# LSU_4_9_OpenAFR_MainBoard.net
KiCad netlist of a schematic drawn in EAGLE
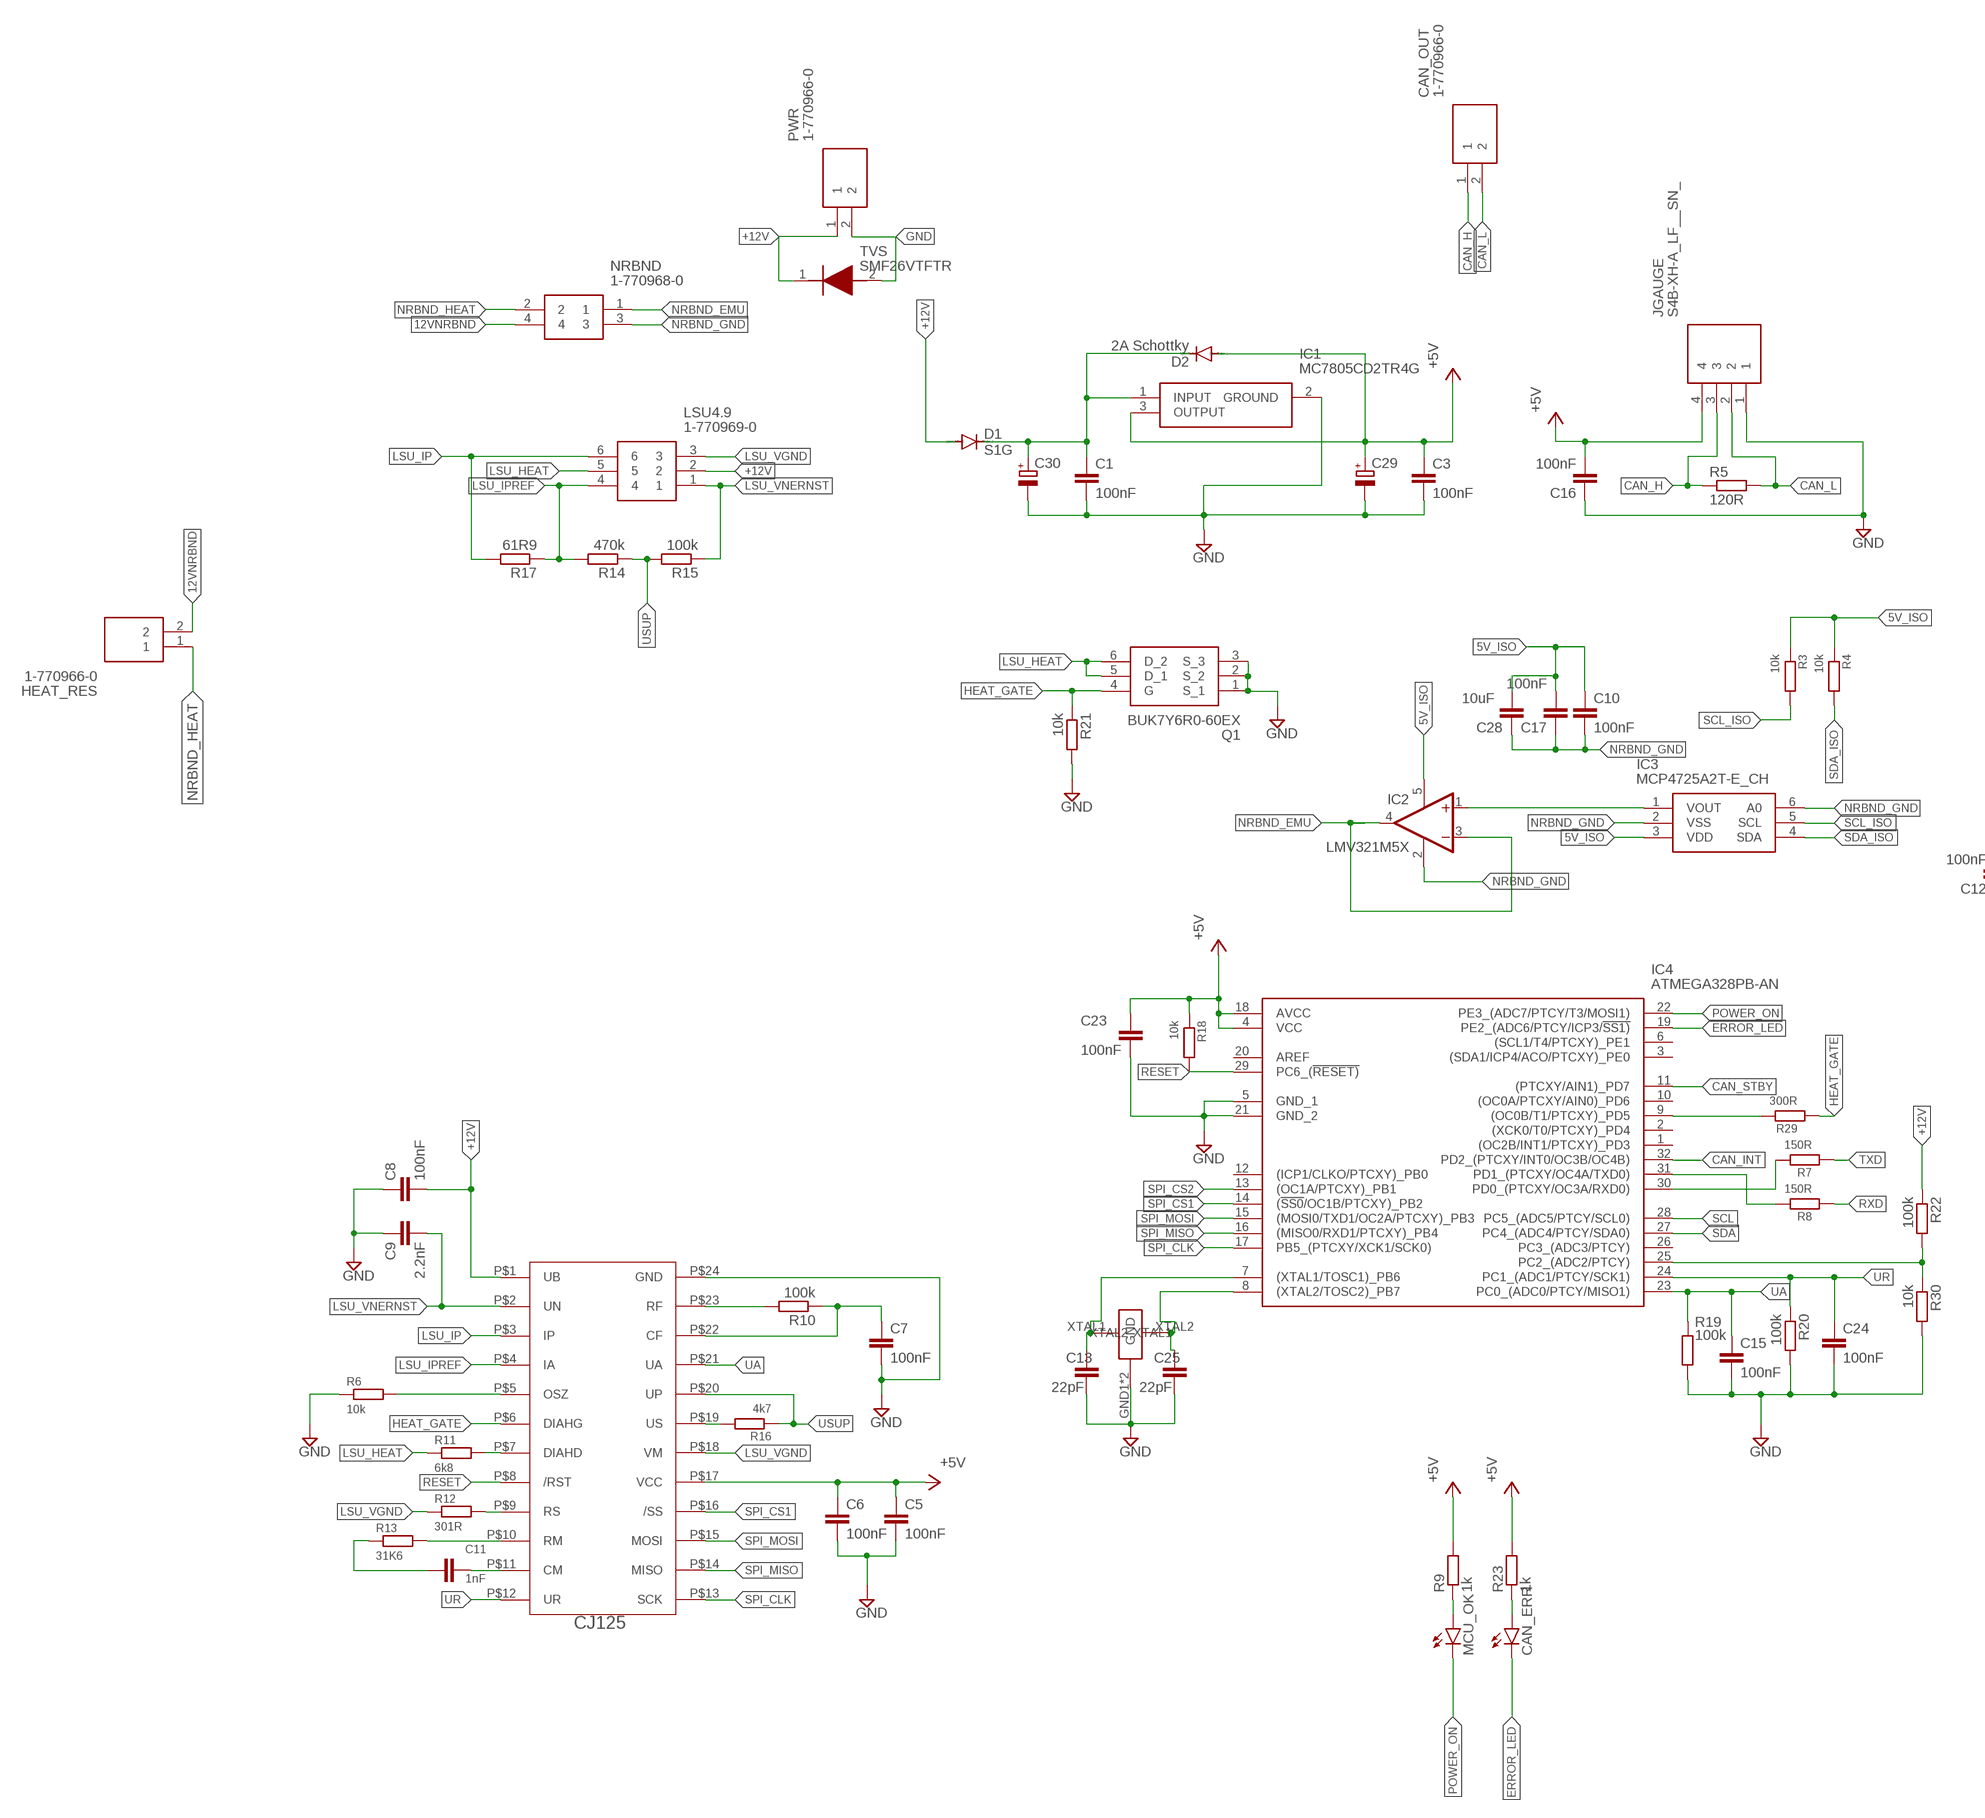
[diagram p0: schematic, sheet 1, part 1 of 2]
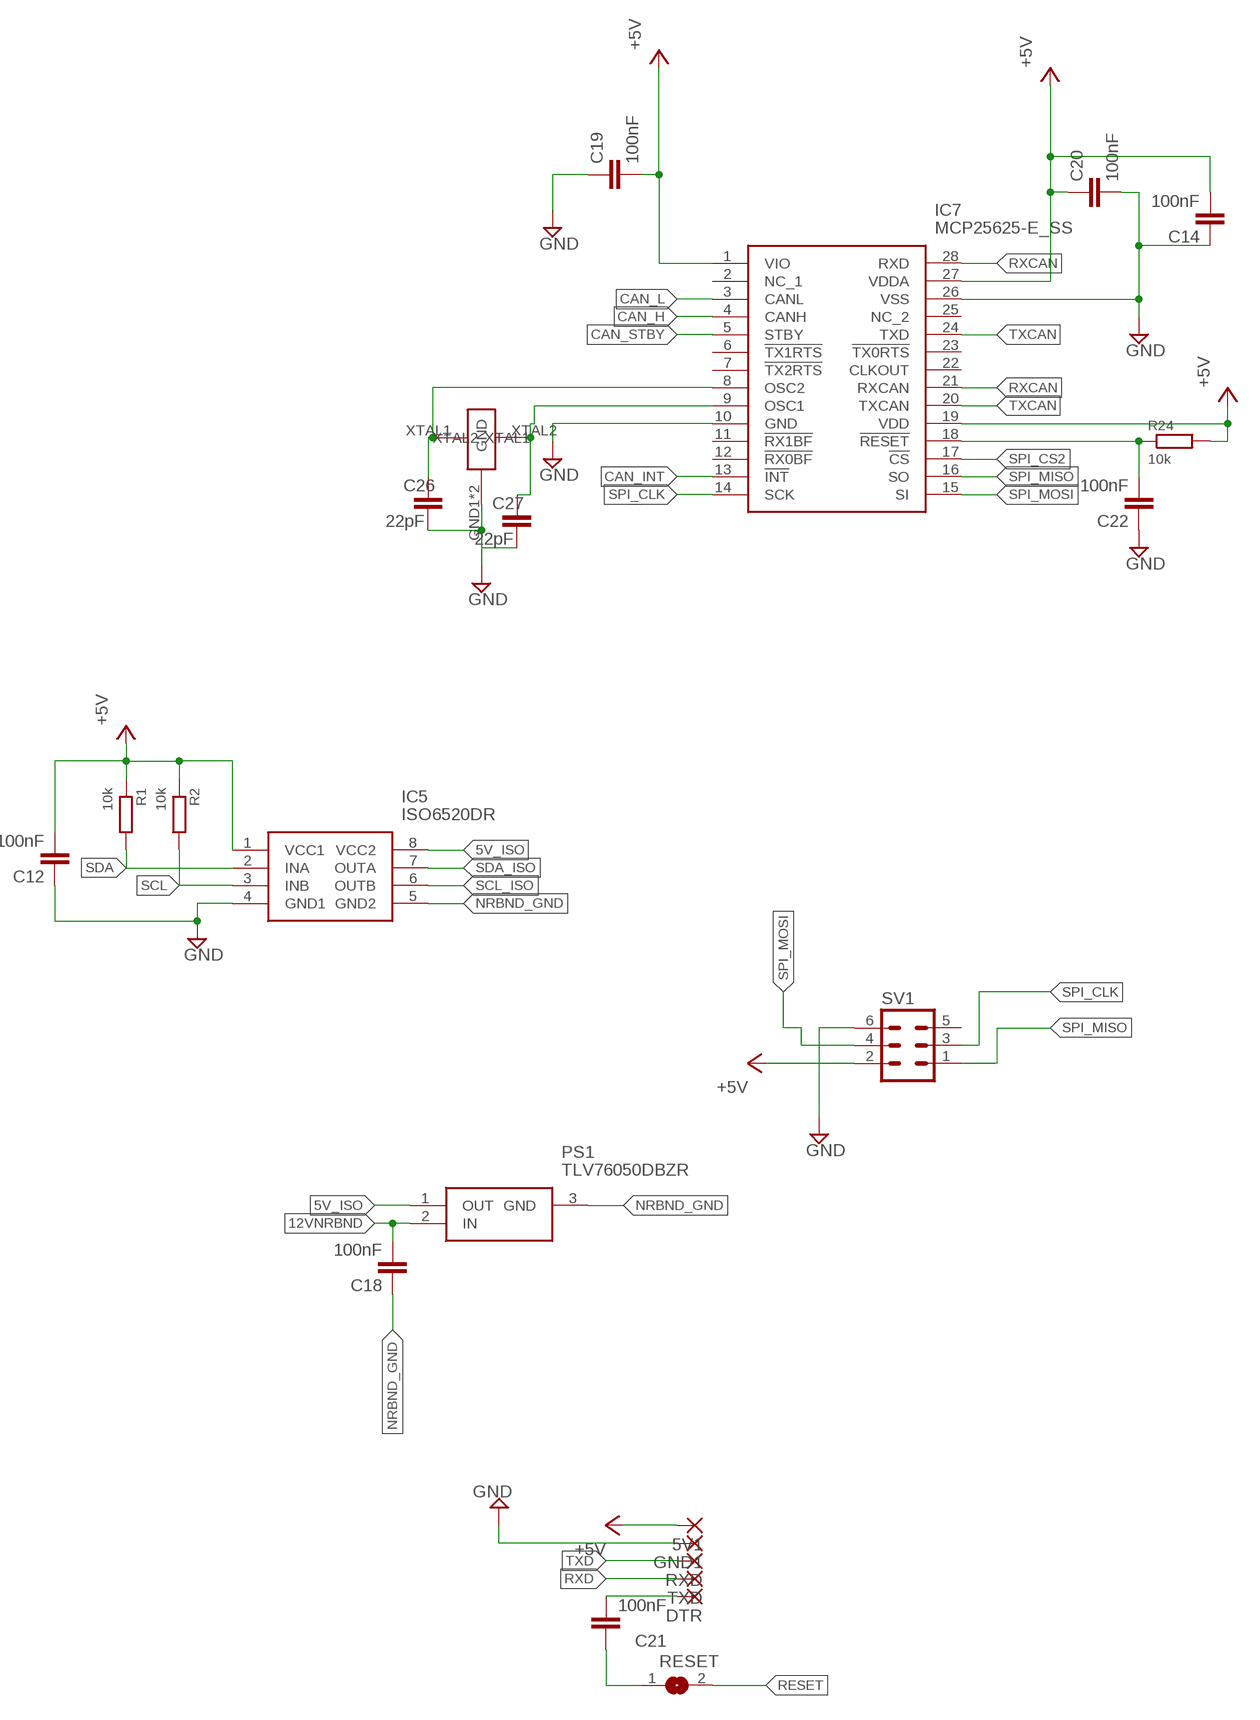
[diagram p1: schematic, sheet 1, part 2 of 2]

(export (version "E")
  (design (tool "Eeschema 10.0.6"))
  (components
    (comp (ref "5V1")
      (value "1,6/0,9")
      (footprint "eagle-import:1,6_0,9")
      (libsource (lib "eagle-import") (part "1,6/0,9"))
    )
    (comp (ref "C1")
      (value "100nF")
      (footprint "eagle-import:C0805")
      (libsource (lib "eagle-import") (part "C-EUC0805"))
    )
    (comp (ref "C3")
      (value "100nF")
      (footprint "eagle-import:C0805")
      (libsource (lib "eagle-import") (part "C-EUC0805"))
    )
    (comp (ref "C5")
      (value "100nF")
      (footprint "eagle-import:C0805")
      (libsource (lib "eagle-import") (part "C-EUC0805"))
    )
    (comp (ref "C6")
      (value "100nF")
      (footprint "eagle-import:C0805")
      (libsource (lib "eagle-import") (part "C-EUC0805"))
    )
    (comp (ref "C7")
      (value "100nF")
      (footprint "eagle-import:C0805")
      (libsource (lib "eagle-import") (part "C-EUC0805"))
    )
    (comp (ref "C8")
      (value "100nF")
      (footprint "eagle-import:C0805")
      (libsource (lib "eagle-import") (part "C-EUC0805"))
    )
    (comp (ref "C9")
      (value "2.2nF")
      (footprint "eagle-import:C0805")
      (libsource (lib "eagle-import") (part "C-EUC0805"))
    )
    (comp (ref "C10")
      (value "100nF")
      (footprint "eagle-import:C0805")
      (libsource (lib "eagle-import") (part "C-EUC0805"))
    )
    (comp (ref "C11")
      (value "1nF")
      (footprint "eagle-import:C0805")
      (libsource (lib "eagle-import") (part "C-EUC0805"))
    )
    (comp (ref "C12")
      (value "100nF")
      (footprint "eagle-import:C0805")
      (libsource (lib "eagle-import") (part "C-EUC0805"))
    )
    (comp (ref "C13")
      (value "22pF")
      (footprint "eagle-import:C0805")
      (libsource (lib "eagle-import") (part "C-EUC0805"))
    )
    (comp (ref "C14")
      (value "100nF")
      (footprint "eagle-import:C0805")
      (libsource (lib "eagle-import") (part "C-EUC0805"))
    )
    (comp (ref "C15")
      (value "100nF")
      (footprint "eagle-import:C0805")
      (libsource (lib "eagle-import") (part "C-EUC0805"))
    )
    (comp (ref "C16")
      (value "100nF")
      (footprint "eagle-import:C0805")
      (libsource (lib "eagle-import") (part "C-EUC0805"))
    )
    (comp (ref "C17")
      (value "100nF")
      (footprint "eagle-import:C0805")
      (libsource (lib "eagle-import") (part "C-EUC0805"))
    )
    (comp (ref "C18")
      (value "100nF")
      (footprint "eagle-import:C0805")
      (libsource (lib "eagle-import") (part "C-EUC0805"))
    )
    (comp (ref "C19")
      (value "100nF")
      (footprint "eagle-import:C0805")
      (libsource (lib "eagle-import") (part "C-EUC0805"))
    )
    (comp (ref "C20")
      (value "100nF")
      (footprint "eagle-import:C0805")
      (libsource (lib "eagle-import") (part "C-EUC0805"))
    )
    (comp (ref "C21")
      (value "100nF")
      (footprint "eagle-import:C0805")
      (libsource (lib "eagle-import") (part "C-EUC0805"))
    )
    (comp (ref "C22")
      (value "100nF")
      (footprint "eagle-import:C0805")
      (libsource (lib "eagle-import") (part "C-EUC0805"))
    )
    (comp (ref "C23")
      (value "100nF")
      (footprint "eagle-import:C0805")
      (libsource (lib "eagle-import") (part "C-EUC0805"))
    )
    (comp (ref "C24")
      (value "100nF")
      (footprint "eagle-import:C0805")
      (libsource (lib "eagle-import") (part "C-EUC0805"))
    )
    (comp (ref "C25")
      (value "22pF")
      (footprint "eagle-import:C0805")
      (libsource (lib "eagle-import") (part "C-EUC0805"))
    )
    (comp (ref "C26")
      (value "22pF")
      (footprint "eagle-import:C0805")
      (libsource (lib "eagle-import") (part "C-EUC0805"))
    )
    (comp (ref "C27")
      (value "22pF")
      (footprint "eagle-import:C0805")
      (libsource (lib "eagle-import") (part "C-EUC0805"))
    )
    (comp (ref "C28")
      (value "10uF")
      (footprint "eagle-import:C0805")
      (libsource (lib "eagle-import") (part "C-EUC0805"))
    )
    (comp (ref "C29")
      (value "CPOL-EU153CLV-0605")
      (footprint "eagle-import:153CLV-0605")
      (libsource (lib "eagle-import") (part "CPOL-EU153CLV-0605"))
    )
    (comp (ref "C30")
      (value "CPOL-EU153CLV-0605")
      (footprint "eagle-import:153CLV-0605")
      (libsource (lib "eagle-import") (part "CPOL-EU153CLV-0605"))
    )
    (comp (ref "CAN_ERR")
      (value "LEDCHIPLED_1206")
      (footprint "eagle-import:CHIPLED_1206")
      (libsource (lib "eagle-import") (part "LEDCHIPLED_1206"))
    )
    (comp (ref "CAN_OUT")
      (value "1-770966-0")
      (footprint "eagle-import:17709660")
      (fields (field (name "MOUSER_PART_NUMBER") "571-1-770966-0"))
      (libsource (lib "eagle-import") (part "1-770966-0"))
    )
    (comp (ref "D1")
      (value "S1G")
      (footprint "eagle-import:DO-214AC")
      (libsource (lib "eagle-import") (part "DIODE-DO-214AC"))
    )
    (comp (ref "D2")
      (value "2A Schottky")
      (footprint "eagle-import:DO-214AC")
      (libsource (lib "eagle-import") (part "DIODE-DO-214AC"))
    )
    (comp (ref "DTR")
      (value "1,6/0,9")
      (footprint "eagle-import:1,6_0,9")
      (libsource (lib "eagle-import") (part "1,6/0,9"))
    )
    (comp (ref "GND1")
      (value "1,6/0,9")
      (footprint "eagle-import:1,6_0,9")
      (libsource (lib "eagle-import") (part "1,6/0,9"))
    )
    (comp (ref "HEAT_RES")
      (value "1-770966-0")
      (footprint "eagle-import:17709660")
      (fields (field (name "MOUSER_PART_NUMBER") "571-1-770966-0"))
      (libsource (lib "eagle-import") (part "1-770966-0"))
    )
    (comp (ref "IC1")
      (value "MC7805CD2TR4G")
      (footprint "eagle-import:MC7805CD2TR4G")
      (fields (field (name "MOUSER_PART_NUMBER") "863-MC7805CD2TR4G"))
      (libsource (lib "eagle-import") (part "MC7805CD2TR4G"))
    )
    (comp (ref "IC2")
      (value "LMV321M5X")
      (footprint "eagle-import:SOT23-5")
      (libsource (lib "eagle-import") (part "LMV321?M5X"))
    )
    (comp (ref "IC3")
      (value "MCP4725A2T-E_CH")
      (footprint "eagle-import:SOT95P270X145-6N")
      (fields
        (field (name "MANUFACTURER_PART_NUMBER") "MCP4725A2T-E/CH")
        (field (name "MOUSER_PART_NUMBER") "579-MCP4725A2T-E/CH")
      )
      (libsource (lib "eagle-import") (part "MCP4725A2T-E_CH"))
    )
    (comp (ref "IC4")
      (value "ATMEGA328PB-AN")
      (footprint "eagle-import:QFP80P900X900X120-32N")
      (fields (field (name "MOUSER_PART_NUMBER") "556-ATMEGA328PB-AN"))
      (libsource (lib "eagle-import") (part "ATMEGA328PB-AN"))
    )
    (comp (ref "IC5")
      (value "ISO6520DR")
      (footprint "eagle-import:SOIC127P600X175-8N")
      (fields (field (name "MOUSER_PART_NUMBER") "595-ISO6520DR"))
      (libsource (lib "eagle-import") (part "ISO6520DR"))
    )
    (comp (ref "IC7")
      (value "MCP25625-E_SS")
      (footprint "eagle-import:SOP65P780X200-28N")
      (fields
        (field (name "MANUFACTURER_PART_NUMBER") "MCP25625-E/SS")
        (field (name "MOUSER_PART_NUMBER") "579-MCP25625-E/SS")
      )
      (libsource (lib "eagle-import") (part "MCP25625-E_SS"))
    )
    (comp (ref "JGAUGE")
      (value "S4B-XH-A_LF__SN_")
      (footprint "eagle-import:S4BXHALFSN")
      (fields (field (name "MANUFACTURER_PART_NUMBER") "S4B-XH-A(LF)(SN)"))
      (libsource (lib "eagle-import") (part "S4B-XH-A_LF__SN_"))
    )
    (comp (ref "LSU4.9")
      (value "1-770969-0")
      (footprint "eagle-import:17709690")
      (fields (field (name "MOUSER_PART_NUMBER") "571-1-770969-0"))
      (libsource (lib "eagle-import") (part "1-770969-0"))
    )
    (comp (ref "MCU_OK")
      (value "LEDCHIPLED_1206")
      (footprint "eagle-import:CHIPLED_1206")
      (libsource (lib "eagle-import") (part "LEDCHIPLED_1206"))
    )
    (comp (ref "NRBND")
      (value "1-770968-0")
      (footprint "eagle-import:17709680")
      (fields (field (name "MOUSER_PART_NUMBER") "571-1-770968-0"))
      (libsource (lib "eagle-import") (part "1-770968-0"))
    )
    (comp (ref "PS1")
      (value "TLV76050DBZR")
      (footprint "eagle-import:SOT95P237X112-3N")
      (fields (field (name "MOUSER_PART_NUMBER") "595-TLV76050DBZR"))
      (libsource (lib "eagle-import") (part "TLV76050DBZR"))
    )
    (comp (ref "PWR")
      (value "1-770966-0")
      (footprint "eagle-import:17709660")
      (fields (field (name "MOUSER_PART_NUMBER") "571-1-770966-0"))
      (libsource (lib "eagle-import") (part "1-770966-0"))
    )
    (comp (ref "Q1")
      (value "BUK7Y6R0-60EX")
      (footprint "eagle-import:BUK7Y6R060EX")
      (fields (field (name "MOUSER_PART_NUMBER") "771-BUK7Y6R0-60EX"))
      (libsource (lib "eagle-import") (part "BUK7Y6R0-60EX"))
    )
    (comp (ref "R1")
      (value "10k")
      (footprint "eagle-import:R0805")
      (libsource (lib "eagle-import") (part "R-EU_R0805"))
    )
    (comp (ref "R2")
      (value "10k")
      (footprint "eagle-import:R0805")
      (libsource (lib "eagle-import") (part "R-EU_R0805"))
    )
    (comp (ref "R3")
      (value "10k")
      (footprint "eagle-import:R0805")
      (libsource (lib "eagle-import") (part "R-EU_R0805"))
    )
    (comp (ref "R4")
      (value "10k")
      (footprint "eagle-import:R0805")
      (libsource (lib "eagle-import") (part "R-EU_R0805"))
    )
    (comp (ref "R5")
      (value "120R")
      (footprint "eagle-import:R1206")
      (libsource (lib "eagle-import") (part "R-EU_R1206"))
    )
    (comp (ref "R6")
      (value "10k")
      (footprint "eagle-import:R0805")
      (libsource (lib "eagle-import") (part "R-EU_R0805"))
    )
    (comp (ref "R7")
      (value "150R")
      (footprint "eagle-import:R0805")
      (libsource (lib "eagle-import") (part "R-EU_R0805"))
    )
    (comp (ref "R8")
      (value "150R")
      (footprint "eagle-import:R0805")
      (libsource (lib "eagle-import") (part "R-EU_R0805"))
    )
    (comp (ref "R9")
      (value "1k")
      (footprint "eagle-import:R0805")
      (libsource (lib "eagle-import") (part "R-EU_R0805"))
    )
    (comp (ref "R10")
      (value "100k")
      (footprint "eagle-import:R0805")
      (libsource (lib "eagle-import") (part "R-EU_R0805"))
    )
    (comp (ref "R11")
      (value "6k8")
      (footprint "eagle-import:R0805")
      (libsource (lib "eagle-import") (part "R-EU_R0805"))
    )
    (comp (ref "R12")
      (value "301R")
      (footprint "eagle-import:R0805")
      (libsource (lib "eagle-import") (part "R-EU_R0805"))
    )
    (comp (ref "R13")
      (value "31K6")
      (footprint "eagle-import:R0805")
      (libsource (lib "eagle-import") (part "R-EU_R0805"))
    )
    (comp (ref "R14")
      (value "470k")
      (footprint "eagle-import:R0805")
      (libsource (lib "eagle-import") (part "R-EU_R0805"))
    )
    (comp (ref "R15")
      (value "100k")
      (footprint "eagle-import:R0805")
      (libsource (lib "eagle-import") (part "R-EU_R0805"))
    )
    (comp (ref "R16")
      (value "4k7")
      (footprint "eagle-import:R0805")
      (libsource (lib "eagle-import") (part "R-EU_R0805"))
    )
    (comp (ref "R17")
      (value "61R9")
      (footprint "eagle-import:R0805")
      (libsource (lib "eagle-import") (part "R-EU_R0805"))
    )
    (comp (ref "R18")
      (value "10k")
      (footprint "eagle-import:R0805")
      (libsource (lib "eagle-import") (part "R-EU_R0805"))
    )
    (comp (ref "R19")
      (value "100k")
      (footprint "eagle-import:R0805")
      (libsource (lib "eagle-import") (part "R-EU_R0805"))
    )
    (comp (ref "R20")
      (value "100k")
      (footprint "eagle-import:R0805")
      (libsource (lib "eagle-import") (part "R-EU_R0805"))
    )
    (comp (ref "R21")
      (value "10k")
      (footprint "eagle-import:R0805")
      (libsource (lib "eagle-import") (part "R-EU_R0805"))
    )
    (comp (ref "R22")
      (value "100k")
      (footprint "eagle-import:R0805")
      (libsource (lib "eagle-import") (part "R-EU_R0805"))
    )
    (comp (ref "R23")
      (value "1k")
      (footprint "eagle-import:R0805")
      (libsource (lib "eagle-import") (part "R-EU_R0805"))
    )
    (comp (ref "R24")
      (value "10k")
      (footprint "eagle-import:R0805")
      (libsource (lib "eagle-import") (part "R-EU_R0805"))
    )
    (comp (ref "R29")
      (value "300R")
      (footprint "eagle-import:R0805")
      (libsource (lib "eagle-import") (part "R-EU_R0805"))
    )
    (comp (ref "R30")
      (value "10k")
      (footprint "eagle-import:R0805")
      (libsource (lib "eagle-import") (part "R-EU_R0805"))
    )
    (comp (ref "RESET")
      (value "SJ")
      (footprint "eagle-import:SJ")
      (libsource (lib "eagle-import") (part "SJ"))
    )
    (comp (ref "RXD")
      (value "1,6/0,9")
      (footprint "eagle-import:1,6_0,9")
      (libsource (lib "eagle-import") (part "1,6/0,9"))
    )
    (comp (ref "SV1")
      (value "MA03-2")
      (footprint "eagle-import:MA03-2")
      (libsource (lib "eagle-import") (part "MA03-2"))
    )
    (comp (ref "TVS")
      (value "SMF26VTFTR")
      (footprint "eagle-import:SMF26VTFTR")
      (fields (field (name "MOUSER_PART_NUMBER") "755-SMF26VTFTR"))
      (libsource (lib "eagle-import") (part "SMF26VTFTR"))
    )
    (comp (ref "TXD")
      (value "1,6/0,9")
      (footprint "eagle-import:1,6_0,9")
      (libsource (lib "eagle-import") (part "1,6/0,9"))
    )
    (comp (ref "U$1")
      (value "CJ125-SOIC24")
      (footprint "eagle-import:CJ125-SOIC24")
      (libsource (lib "eagle-import") (part "CJ125-SOIC24"))
    )
    (comp (ref "U$4")
      (value "E3X160181X04")
      (footprint "eagle-import:E3X160181X04")
      (libsource (lib "eagle-import") (part "E3X160181X04"))
    )
    (comp (ref "U$5")
      (value "E3X160181X04")
      (footprint "eagle-import:E3X160181X04")
      (libsource (lib "eagle-import") (part "E3X160181X04"))
    )
  )
  (nets
    (net (code "1") (name "+5V") (class "Default")
      (node (ref "5V1") (pin "1") (pinfunction "P_1") (pintype "passive"))
      (node (ref "C12") (pin "2") (pinfunction "2_2") (pintype "passive"))
      (node (ref "C14") (pin "2") (pinfunction "2_2") (pintype "passive"))
      (node (ref "C16") (pin "2") (pinfunction "2_2") (pintype "passive"))
      (node (ref "C19") (pin "2") (pinfunction "2_2") (pintype "passive"))
      (node (ref "C20") (pin "1") (pinfunction "1_1") (pintype "passive"))
      (node (ref "C23") (pin "1") (pinfunction "1_1") (pintype "passive"))
      (node (ref "C29") (pin "+") (pinfunction "+_+") (pintype "passive"))
      (node (ref "C3") (pin "1") (pinfunction "1_1") (pintype "passive"))
      (node (ref "C5") (pin "1") (pinfunction "1_1") (pintype "passive"))
      (node (ref "C6") (pin "1") (pinfunction "1_1") (pintype "passive"))
      (node (ref "D2") (pin "A") (pinfunction "A_A") (pintype "passive"))
      (node (ref "IC1") (pin "3") (pinfunction "OUTPUT_3") (pintype "bidirectional"))
      (node (ref "IC4") (pin "18") (pinfunction "AVCC_18") (pintype "bidirectional"))
      (node (ref "IC4") (pin "4") (pinfunction "VCC_4") (pintype "bidirectional"))
      (node (ref "IC5") (pin "1") (pinfunction "VCC1_1") (pintype "bidirectional"))
      (node (ref "IC7") (pin "1") (pinfunction "VIO_1") (pintype "bidirectional"))
      (node (ref "IC7") (pin "19") (pinfunction "VDD_19") (pintype "bidirectional"))
      (node (ref "IC7") (pin "27") (pinfunction "VDDA_27") (pintype "bidirectional"))
      (node (ref "JGAUGE") (pin "4") (pinfunction "4_4") (pintype "bidirectional"))
      (node (ref "R1") (pin "1") (pinfunction "1_1") (pintype "passive"))
      (node (ref "R18") (pin "1") (pinfunction "1_1") (pintype "passive"))
      (node (ref "R2") (pin "1") (pinfunction "1_1") (pintype "passive"))
      (node (ref "R23") (pin "2") (pinfunction "2_2") (pintype "passive"))
      (node (ref "R24") (pin "2") (pinfunction "2_2") (pintype "passive"))
      (node (ref "R9") (pin "2") (pinfunction "2_2") (pintype "passive"))
      (node (ref "SV1") (pin "2") (pinfunction "2_2") (pintype "passive"))
      (node (ref "U$1") (pin "P$17") (pinfunction "VCC_P$17") (pintype "bidirectional"))
    )
    (net (code "2") (name "+12V") (class "Default")
      (node (ref "C8") (pin "2") (pinfunction "2_2") (pintype "passive"))
      (node (ref "D1") (pin "A") (pinfunction "A_A") (pintype "passive"))
      (node (ref "LSU4.9") (pin "2") (pinfunction "2_2") (pintype "bidirectional"))
      (node (ref "PWR") (pin "1") (pinfunction "1_1") (pintype "bidirectional"))
      (node (ref "R22") (pin "1") (pinfunction "1_1") (pintype "passive"))
      (node (ref "TVS") (pin "1") (pinfunction "K_1") (pintype "bidirectional"))
      (node (ref "U$1") (pin "P$1") (pinfunction "UB_P$1") (pintype "bidirectional"))
    )
    (net (code "3") (name "5V_ISO") (class "Default")
      (node (ref "C10") (pin "1") (pinfunction "1_1") (pintype "passive"))
      (node (ref "C17") (pin "2") (pinfunction "2_2") (pintype "passive"))
      (node (ref "C28") (pin "1") (pinfunction "1_1") (pintype "passive"))
      (node (ref "IC2") (pin "5") (pinfunction "V+_5") (pintype "power_in"))
      (node (ref "IC3") (pin "3") (pinfunction "VDD_3") (pintype "bidirectional"))
      (node (ref "IC5") (pin "8") (pinfunction "VCC2_8") (pintype "bidirectional"))
      (node (ref "PS1") (pin "1") (pinfunction "OUT_1") (pintype "output"))
      (node (ref "R3") (pin "1") (pinfunction "1_1") (pintype "passive"))
      (node (ref "R4") (pin "1") (pinfunction "1_1") (pintype "passive"))
    )
    (net (code "4") (name "12VNRBND") (class "Default")
      (node (ref "C18") (pin "2") (pinfunction "2_2") (pintype "passive"))
      (node (ref "HEAT_RES") (pin "2") (pinfunction "2_2") (pintype "bidirectional"))
      (node (ref "NRBND") (pin "4") (pinfunction "4_4") (pintype "bidirectional"))
      (node (ref "PS1") (pin "2") (pinfunction "IN_2") (pintype "input"))
    )
    (net (code "5") (name "CAN_H") (class "Default")
      (node (ref "CAN_OUT") (pin "1") (pinfunction "1_1") (pintype "bidirectional"))
      (node (ref "IC7") (pin "4") (pinfunction "CANH_4") (pintype "bidirectional"))
      (node (ref "JGAUGE") (pin "3") (pinfunction "3_3") (pintype "bidirectional"))
      (node (ref "R5") (pin "1") (pinfunction "1_1") (pintype "passive"))
    )
    (net (code "6") (name "CAN_INT") (class "Default")
      (node (ref "IC4") (pin "32") (pinfunction "PD2_(PTCXY/INT0/OC3B/OC4B)_32") (pintype "bidirectional"))
      (node (ref "IC7") (pin "13") (pinfunction "~{INT}_13") (pintype "bidirectional"))
    )
    (net (code "7") (name "CAN_L") (class "Default")
      (node (ref "CAN_OUT") (pin "2") (pinfunction "2_2") (pintype "bidirectional"))
      (node (ref "IC7") (pin "3") (pinfunction "CANL_3") (pintype "bidirectional"))
      (node (ref "JGAUGE") (pin "2") (pinfunction "2_2") (pintype "bidirectional"))
      (node (ref "R5") (pin "2") (pinfunction "2_2") (pintype "passive"))
    )
    (net (code "8") (name "CAN_STBY") (class "Default")
      (node (ref "IC4") (pin "11") (pinfunction "(PTCXY/AIN1)_PD7_11") (pintype "bidirectional"))
      (node (ref "IC7") (pin "5") (pinfunction "STBY_5") (pintype "bidirectional"))
    )
    (net (code "9") (name "ERROR_LED") (class "Default")
      (node (ref "CAN_ERR") (pin "C") (pinfunction "C_C") (pintype "passive"))
      (node (ref "IC4") (pin "19") (pinfunction "PE2_(ADC6/PTCY/ICP3/~{SS1})_19") (pintype "bidirectional"))
    )
    (net (code "10") (name "GND") (class "Default")
      (node (ref "C1") (pin "2") (pinfunction "2_2") (pintype "passive"))
      (node (ref "C12") (pin "1") (pinfunction "1_1") (pintype "passive"))
      (node (ref "C13") (pin "2") (pinfunction "2_2") (pintype "passive"))
      (node (ref "C14") (pin "1") (pinfunction "1_1") (pintype "passive"))
      (node (ref "C15") (pin "2") (pinfunction "2_2") (pintype "passive"))
      (node (ref "C16") (pin "1") (pinfunction "1_1") (pintype "passive"))
      (node (ref "C19") (pin "1") (pinfunction "1_1") (pintype "passive"))
      (node (ref "C20") (pin "2") (pinfunction "2_2") (pintype "passive"))
      (node (ref "C22") (pin "1") (pinfunction "1_1") (pintype "passive"))
      (node (ref "C23") (pin "2") (pinfunction "2_2") (pintype "passive"))
      (node (ref "C24") (pin "2") (pinfunction "2_2") (pintype "passive"))
      (node (ref "C25") (pin "2") (pinfunction "2_2") (pintype "passive"))
      (node (ref "C26") (pin "2") (pinfunction "2_2") (pintype "passive"))
      (node (ref "C27") (pin "2") (pinfunction "2_2") (pintype "passive"))
      (node (ref "C29") (pin "-") (pinfunction "-_-") (pintype "passive"))
      (node (ref "C3") (pin "2") (pinfunction "2_2") (pintype "passive"))
      (node (ref "C30") (pin "-") (pinfunction "-_-") (pintype "passive"))
      (node (ref "C5") (pin "2") (pinfunction "2_2") (pintype "passive"))
      (node (ref "C6") (pin "2") (pinfunction "2_2") (pintype "passive"))
      (node (ref "C7") (pin "2") (pinfunction "2_2") (pintype "passive"))
      (node (ref "C8") (pin "1") (pinfunction "1_1") (pintype "passive"))
      (node (ref "C9") (pin "2") (pinfunction "2_2") (pintype "passive"))
      (node (ref "GND1") (pin "1") (pinfunction "P_1") (pintype "passive"))
      (node (ref "IC1") (pin "2") (pinfunction "GROUND_2") (pintype "bidirectional"))
      (node (ref "IC4") (pin "21") (pinfunction "GND_2_21") (pintype "bidirectional"))
      (node (ref "IC4") (pin "5") (pinfunction "GND_1_5") (pintype "bidirectional"))
      (node (ref "IC5") (pin "4") (pinfunction "GND1_4") (pintype "bidirectional"))
      (node (ref "IC7") (pin "10") (pinfunction "GND_10") (pintype "bidirectional"))
      (node (ref "IC7") (pin "26") (pinfunction "VSS_26") (pintype "bidirectional"))
      (node (ref "JGAUGE") (pin "1") (pinfunction "1_1") (pintype "bidirectional"))
      (node (ref "PWR") (pin "2") (pinfunction "2_2") (pintype "bidirectional"))
      (node (ref "Q1") (pin "1") (pinfunction "S_1_1") (pintype "bidirectional"))
      (node (ref "Q1") (pin "2") (pinfunction "S_2_2") (pintype "bidirectional"))
      (node (ref "Q1") (pin "3") (pinfunction "S_3_3") (pintype "bidirectional"))
      (node (ref "R19") (pin "2") (pinfunction "2_2") (pintype "passive"))
      (node (ref "R20") (pin "2") (pinfunction "2_2") (pintype "passive"))
      (node (ref "R21") (pin "2") (pinfunction "2_2") (pintype "passive"))
      (node (ref "R30") (pin "2") (pinfunction "2_2") (pintype "passive"))
      (node (ref "R6") (pin "1") (pinfunction "1_1") (pintype "passive"))
      (node (ref "SV1") (pin "6") (pinfunction "6_6") (pintype "passive"))
      (node (ref "TVS") (pin "2") (pinfunction "A_2") (pintype "bidirectional"))
      (node (ref "U$1") (pin "P$24") (pinfunction "GND_P$24") (pintype "bidirectional"))
      (node (ref "U$4") (pin "GND1") (pinfunction "GND_GND1") (pintype "bidirectional"))
      (node (ref "U$4") (pin "GND2") (pinfunction "GND_GND2") (pintype "bidirectional"))
      (node (ref "U$5") (pin "GND1") (pinfunction "GND_GND1") (pintype "bidirectional"))
      (node (ref "U$5") (pin "GND2") (pinfunction "GND_GND2") (pintype "bidirectional"))
    )
    (net (code "11") (name "HEAT_GATE") (class "Default")
      (node (ref "Q1") (pin "4") (pinfunction "G_4") (pintype "bidirectional"))
      (node (ref "R21") (pin "1") (pinfunction "1_1") (pintype "passive"))
      (node (ref "R29") (pin "1") (pinfunction "1_1") (pintype "passive"))
      (node (ref "U$1") (pin "P$6") (pinfunction "DIAHG_P$6") (pintype "bidirectional"))
    )
    (net (code "12") (name "LSU_HEAT") (class "Default")
      (node (ref "LSU4.9") (pin "5") (pinfunction "5_5") (pintype "bidirectional"))
      (node (ref "Q1") (pin "5") (pinfunction "D_1_5") (pintype "bidirectional"))
      (node (ref "Q1") (pin "6") (pinfunction "D_2_6") (pintype "bidirectional"))
      (node (ref "R11") (pin "1") (pinfunction "1_1") (pintype "passive"))
    )
    (net (code "13") (name "LSU_IP") (class "Default")
      (node (ref "LSU4.9") (pin "6") (pinfunction "6_6") (pintype "bidirectional"))
      (node (ref "R17") (pin "2") (pinfunction "2_2") (pintype "passive"))
      (node (ref "U$1") (pin "P$3") (pinfunction "IP_P$3") (pintype "bidirectional"))
    )
    (net (code "14") (name "LSU_IPREF") (class "Default")
      (node (ref "LSU4.9") (pin "4") (pinfunction "4_4") (pintype "bidirectional"))
      (node (ref "R14") (pin "2") (pinfunction "2_2") (pintype "passive"))
      (node (ref "R17") (pin "1") (pinfunction "1_1") (pintype "passive"))
      (node (ref "U$1") (pin "P$4") (pinfunction "IA_P$4") (pintype "bidirectional"))
    )
    (net (code "15") (name "LSU_VGND") (class "Default")
      (node (ref "LSU4.9") (pin "3") (pinfunction "3_3") (pintype "bidirectional"))
      (node (ref "R12") (pin "1") (pinfunction "1_1") (pintype "passive"))
      (node (ref "U$1") (pin "P$18") (pinfunction "VM_P$18") (pintype "bidirectional"))
    )
    (net (code "16") (name "LSU_VNERNST") (class "Default")
      (node (ref "C9") (pin "1") (pinfunction "1_1") (pintype "passive"))
      (node (ref "LSU4.9") (pin "1") (pinfunction "1_1") (pintype "bidirectional"))
      (node (ref "R15") (pin "1") (pinfunction "1_1") (pintype "passive"))
      (node (ref "U$1") (pin "P$2") (pinfunction "UN_P$2") (pintype "bidirectional"))
    )
    (net (code "17") (name "NRBND_EMU") (class "Default")
      (node (ref "IC2") (pin "3") (pinfunction "-IN_3") (pintype "input"))
      (node (ref "IC2") (pin "4") (pinfunction "OUT_4") (pintype "output"))
      (node (ref "NRBND") (pin "1") (pinfunction "1_1") (pintype "bidirectional"))
    )
    (net (code "18") (name "NRBND_GND") (class "Default")
      (node (ref "C10") (pin "2") (pinfunction "2_2") (pintype "passive"))
      (node (ref "C17") (pin "1") (pinfunction "1_1") (pintype "passive"))
      (node (ref "C18") (pin "1") (pinfunction "1_1") (pintype "passive"))
      (node (ref "C28") (pin "2") (pinfunction "2_2") (pintype "passive"))
      (node (ref "IC2") (pin "2") (pinfunction "V-_2") (pintype "power_in"))
      (node (ref "IC3") (pin "2") (pinfunction "VSS_2") (pintype "bidirectional"))
      (node (ref "IC3") (pin "6") (pinfunction "A0_6") (pintype "bidirectional"))
      (node (ref "IC5") (pin "5") (pinfunction "GND2_5") (pintype "bidirectional"))
      (node (ref "NRBND") (pin "3") (pinfunction "3_3") (pintype "bidirectional"))
      (node (ref "PS1") (pin "3") (pinfunction "GND_3") (pintype "power_in"))
    )
    (net (code "19") (name "NRBND_HEAT") (class "Default")
      (node (ref "HEAT_RES") (pin "1") (pinfunction "1_1") (pintype "bidirectional"))
      (node (ref "NRBND") (pin "2") (pinfunction "2_2") (pintype "bidirectional"))
    )
    (net (code "20") (name "Net-(C11-Pad1)") (class "Default")
      (node (ref "C11") (pin "1") (pinfunction "1_1") (pintype "passive"))
      (node (ref "R13") (pin "1") (pinfunction "1_1") (pintype "passive"))
    )
    (net (code "21") (name "Net-(C21-Pad1)") (class "Default")
      (node (ref "C21") (pin "1") (pinfunction "1_1") (pintype "passive"))
      (node (ref "RESET") (pin "1") (pinfunction "1_1") (pintype "passive"))
    )
    (net (code "22") (name "Net-(CAN_ERR-PadA)") (class "Default")
      (node (ref "CAN_ERR") (pin "A") (pinfunction "A_A") (pintype "passive"))
      (node (ref "R23") (pin "1") (pinfunction "1_1") (pintype "passive"))
    )
    (net (code "23") (name "Net-(DTR-P)") (class "Default")
      (node (ref "C21") (pin "2") (pinfunction "2_2") (pintype "passive"))
      (node (ref "DTR") (pin "1") (pinfunction "P_1") (pintype "passive"))
    )
    (net (code "24") (name "Net-(IC1-INPUT)") (class "Default")
      (node (ref "C1") (pin "1") (pinfunction "1_1") (pintype "passive"))
      (node (ref "C30") (pin "+") (pinfunction "+_+") (pintype "passive"))
      (node (ref "D1") (pin "C") (pinfunction "C_C") (pintype "passive"))
      (node (ref "D2") (pin "C") (pinfunction "C_C") (pintype "passive"))
      (node (ref "IC1") (pin "1") (pinfunction "INPUT_1") (pintype "bidirectional"))
    )
    (net (code "25") (name "Net-(IC2-+IN)") (class "Default")
      (node (ref "IC2") (pin "1") (pinfunction "+IN_1") (pintype "input"))
      (node (ref "IC3") (pin "1") (pinfunction "VOUT_1") (pintype "bidirectional"))
    )
    (net (code "26") (name "Net-(IC4-(OC0B{slash}T1{slash}PTCXY)_PD5)") (class "Default")
      (node (ref "IC4") (pin "9") (pinfunction "(OC0B/T1/PTCXY)_PD5_9") (pintype "bidirectional"))
      (node (ref "R29") (pin "2") (pinfunction "2_2") (pintype "passive"))
    )
    (net (code "27") (name "Net-(IC4-(XTAL1{slash}TOSC1)_PB6)") (class "Default")
      (node (ref "C13") (pin "1") (pinfunction "1_1") (pintype "passive"))
      (node (ref "IC4") (pin "7") (pinfunction "(XTAL1/TOSC1)_PB6_7") (pintype "bidirectional"))
      (node (ref "U$4") (pin "XTAL1") (pinfunction "XTAL1_XTAL1") (pintype "bidirectional"))
    )
    (net (code "28") (name "Net-(IC4-(XTAL2{slash}TOSC2)_PB7)") (class "Default")
      (node (ref "C25") (pin "1") (pinfunction "1_1") (pintype "passive"))
      (node (ref "IC4") (pin "8") (pinfunction "(XTAL2/TOSC2)_PB7_8") (pintype "bidirectional"))
      (node (ref "U$4") (pin "XTAL2") (pinfunction "XTAL2_XTAL2") (pintype "bidirectional"))
    )
    (net (code "29") (name "Net-(IC4-PC2_(ADC2{slash}PTCY))") (class "Default")
      (node (ref "IC4") (pin "25") (pinfunction "PC2_(ADC2/PTCY)_25") (pintype "bidirectional"))
      (node (ref "R22") (pin "2") (pinfunction "2_2") (pintype "passive"))
      (node (ref "R30") (pin "1") (pinfunction "1_1") (pintype "passive"))
    )
    (net (code "30") (name "Net-(IC4-PD0_(PTCXY{slash}OC3A{slash}RXD0))") (class "Default")
      (node (ref "IC4") (pin "30") (pinfunction "PD0_(PTCXY/OC3A/RXD0)_30") (pintype "bidirectional"))
      (node (ref "R7") (pin "2") (pinfunction "2_2") (pintype "passive"))
    )
    (net (code "31") (name "Net-(IC4-PD1_(PTCXY{slash}OC4A{slash}TXD0))") (class "Default")
      (node (ref "IC4") (pin "31") (pinfunction "PD1_(PTCXY/OC4A/TXD0)_31") (pintype "bidirectional"))
      (node (ref "R8") (pin "2") (pinfunction "2_2") (pintype "passive"))
    )
    (net (code "32") (name "Net-(IC7-OSC1)") (class "Default")
      (node (ref "C27") (pin "1") (pinfunction "1_1") (pintype "passive"))
      (node (ref "IC7") (pin "9") (pinfunction "OSC1_9") (pintype "bidirectional"))
      (node (ref "U$5") (pin "XTAL2") (pinfunction "XTAL2_XTAL2") (pintype "bidirectional"))
    )
    (net (code "33") (name "Net-(IC7-OSC2)") (class "Default")
      (node (ref "C26") (pin "1") (pinfunction "1_1") (pintype "passive"))
      (node (ref "IC7") (pin "8") (pinfunction "OSC2_8") (pintype "bidirectional"))
      (node (ref "U$5") (pin "XTAL1") (pinfunction "XTAL1_XTAL1") (pintype "bidirectional"))
    )
    (net (code "34") (name "Net-(IC7-~{RESET})") (class "Default")
      (node (ref "C22") (pin "2") (pinfunction "2_2") (pintype "passive"))
      (node (ref "IC7") (pin "18") (pinfunction "~{RESET}_18") (pintype "bidirectional"))
      (node (ref "R24") (pin "1") (pinfunction "1_1") (pintype "passive"))
    )
    (net (code "35") (name "Net-(MCU_OK-PadA)") (class "Default")
      (node (ref "MCU_OK") (pin "A") (pinfunction "A_A") (pintype "passive"))
      (node (ref "R9") (pin "1") (pinfunction "1_1") (pintype "passive"))
    )
    (net (code "36") (name "Net-(U$1-CF)") (class "Default")
      (node (ref "C7") (pin "1") (pinfunction "1_1") (pintype "passive"))
      (node (ref "R10") (pin "1") (pinfunction "1_1") (pintype "passive"))
      (node (ref "U$1") (pin "P$22") (pinfunction "CF_P$22") (pintype "bidirectional"))
    )
    (net (code "37") (name "Net-(U$1-CM)") (class "Default")
      (node (ref "C11") (pin "2") (pinfunction "2_2") (pintype "passive"))
      (node (ref "U$1") (pin "P$11") (pinfunction "CM_P$11") (pintype "bidirectional"))
    )
    (net (code "38") (name "Net-(U$1-DIAHD)") (class "Default")
      (node (ref "R11") (pin "2") (pinfunction "2_2") (pintype "passive"))
      (node (ref "U$1") (pin "P$7") (pinfunction "DIAHD_P$7") (pintype "bidirectional"))
    )
    (net (code "39") (name "Net-(U$1-OSZ)") (class "Default")
      (node (ref "R6") (pin "2") (pinfunction "2_2") (pintype "passive"))
      (node (ref "U$1") (pin "P$5") (pinfunction "OSZ_P$5") (pintype "bidirectional"))
    )
    (net (code "40") (name "Net-(U$1-RF)") (class "Default")
      (node (ref "R10") (pin "2") (pinfunction "2_2") (pintype "passive"))
      (node (ref "U$1") (pin "P$23") (pinfunction "RF_P$23") (pintype "bidirectional"))
    )
    (net (code "41") (name "Net-(U$1-RM)") (class "Default")
      (node (ref "R13") (pin "2") (pinfunction "2_2") (pintype "passive"))
      (node (ref "U$1") (pin "P$10") (pinfunction "RM_P$10") (pintype "bidirectional"))
    )
    (net (code "42") (name "Net-(U$1-RS)") (class "Default")
      (node (ref "R12") (pin "2") (pinfunction "2_2") (pintype "passive"))
      (node (ref "U$1") (pin "P$9") (pinfunction "RS_P$9") (pintype "bidirectional"))
    )
    (net (code "43") (name "Net-(U$1-US)") (class "Default")
      (node (ref "R16") (pin "2") (pinfunction "2_2") (pintype "passive"))
      (node (ref "U$1") (pin "P$19") (pinfunction "US_P$19") (pintype "bidirectional"))
    )
    (net (code "44") (name "POWER_ON") (class "Default")
      (node (ref "IC4") (pin "22") (pinfunction "PE3_(ADC7/PTCY/T3/MOSI1)_22") (pintype "bidirectional"))
      (node (ref "MCU_OK") (pin "C") (pinfunction "C_C") (pintype "passive"))
    )
    (net (code "45") (name "RESET") (class "Default")
      (node (ref "IC4") (pin "29") (pinfunction "PC6_(~{RESET})_29") (pintype "bidirectional"))
      (node (ref "R18") (pin "2") (pinfunction "2_2") (pintype "passive"))
      (node (ref "RESET") (pin "2") (pinfunction "2_2") (pintype "passive"))
      (node (ref "U$1") (pin "P$8") (pinfunction "/RST_P$8") (pintype "bidirectional"))
    )
    (net (code "46") (name "RXCAN") (class "Default")
      (node (ref "IC7") (pin "21") (pinfunction "RXCAN_21") (pintype "bidirectional"))
      (node (ref "IC7") (pin "28") (pinfunction "RXD_28") (pintype "bidirectional"))
    )
    (net (code "47") (name "RXD") (class "Default")
      (node (ref "R8") (pin "1") (pinfunction "1_1") (pintype "passive"))
      (node (ref "TXD") (pin "1") (pinfunction "P_1") (pintype "passive"))
    )
    (net (code "48") (name "SCL") (class "Default")
      (node (ref "IC4") (pin "28") (pinfunction "PC5_(ADC5/PTCY/SCL0)_28") (pintype "bidirectional"))
      (node (ref "IC5") (pin "3") (pinfunction "INB_3") (pintype "bidirectional"))
      (node (ref "R2") (pin "2") (pinfunction "2_2") (pintype "passive"))
    )
    (net (code "49") (name "SCL_ISO") (class "Default")
      (node (ref "IC3") (pin "5") (pinfunction "SCL_5") (pintype "bidirectional"))
      (node (ref "IC5") (pin "6") (pinfunction "OUTB_6") (pintype "bidirectional"))
      (node (ref "R3") (pin "2") (pinfunction "2_2") (pintype "passive"))
    )
    (net (code "50") (name "SDA") (class "Default")
      (node (ref "IC4") (pin "27") (pinfunction "PC4_(ADC4/PTCY/SDA0)_27") (pintype "bidirectional"))
      (node (ref "IC5") (pin "2") (pinfunction "INA_2") (pintype "bidirectional"))
      (node (ref "R1") (pin "2") (pinfunction "2_2") (pintype "passive"))
    )
    (net (code "51") (name "SDA_ISO") (class "Default")
      (node (ref "IC3") (pin "4") (pinfunction "SDA_4") (pintype "bidirectional"))
      (node (ref "IC5") (pin "7") (pinfunction "OUTA_7") (pintype "bidirectional"))
      (node (ref "R4") (pin "2") (pinfunction "2_2") (pintype "passive"))
    )
    (net (code "52") (name "SPI_CLK") (class "Default")
      (node (ref "IC4") (pin "17") (pinfunction "PB5_(PTCXY/XCK1/SCK0)_17") (pintype "bidirectional"))
      (node (ref "IC7") (pin "14") (pinfunction "SCK_14") (pintype "bidirectional"))
      (node (ref "SV1") (pin "3") (pinfunction "3_3") (pintype "passive"))
      (node (ref "U$1") (pin "P$13") (pinfunction "SCK_P$13") (pintype "bidirectional"))
    )
    (net (code "53") (name "SPI_CS1") (class "Default")
      (node (ref "IC4") (pin "14") (pinfunction "(~{SS0}/OC1B/PTCXY)_PB2_14") (pintype "bidirectional"))
      (node (ref "U$1") (pin "P$16") (pinfunction "/SS_P$16") (pintype "bidirectional"))
    )
    (net (code "54") (name "SPI_CS2") (class "Default")
      (node (ref "IC4") (pin "13") (pinfunction "(OC1A/PTCXY)_PB1_13") (pintype "bidirectional"))
      (node (ref "IC7") (pin "17") (pinfunction "~{CS}_17") (pintype "bidirectional"))
    )
    (net (code "55") (name "SPI_MISO") (class "Default")
      (node (ref "IC4") (pin "16") (pinfunction "(MISO0/RXD1/PTCXY)_PB4_16") (pintype "bidirectional"))
      (node (ref "IC7") (pin "16") (pinfunction "SO_16") (pintype "bidirectional"))
      (node (ref "SV1") (pin "1") (pinfunction "1_1") (pintype "passive"))
      (node (ref "U$1") (pin "P$14") (pinfunction "MISO_P$14") (pintype "bidirectional"))
    )
    (net (code "56") (name "SPI_MOSI") (class "Default")
      (node (ref "IC4") (pin "15") (pinfunction "(MOSI0/TXD1/OC2A/PTCXY)_PB3_15") (pintype "bidirectional"))
      (node (ref "IC7") (pin "15") (pinfunction "SI_15") (pintype "bidirectional"))
      (node (ref "SV1") (pin "4") (pinfunction "4_4") (pintype "passive"))
      (node (ref "U$1") (pin "P$15") (pinfunction "MOSI_P$15") (pintype "bidirectional"))
    )
    (net (code "57") (name "TXCAN") (class "Default")
      (node (ref "IC7") (pin "20") (pinfunction "TXCAN_20") (pintype "bidirectional"))
      (node (ref "IC7") (pin "24") (pinfunction "TXD_24") (pintype "bidirectional"))
    )
    (net (code "58") (name "TXD") (class "Default")
      (node (ref "R7") (pin "1") (pinfunction "1_1") (pintype "passive"))
      (node (ref "RXD") (pin "1") (pinfunction "P_1") (pintype "passive"))
    )
    (net (code "59") (name "UA") (class "Default")
      (node (ref "C15") (pin "1") (pinfunction "1_1") (pintype "passive"))
      (node (ref "IC4") (pin "23") (pinfunction "PC0_(ADC0/PTCY/MISO1)_23") (pintype "bidirectional"))
      (node (ref "R19") (pin "1") (pinfunction "1_1") (pintype "passive"))
      (node (ref "U$1") (pin "P$21") (pinfunction "UA_P$21") (pintype "bidirectional"))
    )
    (net (code "60") (name "UR") (class "Default")
      (node (ref "C24") (pin "1") (pinfunction "1_1") (pintype "passive"))
      (node (ref "IC4") (pin "24") (pinfunction "PC1_(ADC1/PTCY/SCK1)_24") (pintype "bidirectional"))
      (node (ref "R20") (pin "1") (pinfunction "1_1") (pintype "passive"))
      (node (ref "U$1") (pin "P$12") (pinfunction "UR_P$12") (pintype "bidirectional"))
    )
    (net (code "61") (name "USUP") (class "Default")
      (node (ref "R14") (pin "1") (pinfunction "1_1") (pintype "passive"))
      (node (ref "R15") (pin "2") (pinfunction "2_2") (pintype "passive"))
      (node (ref "R16") (pin "1") (pinfunction "1_1") (pintype "passive"))
      (node (ref "U$1") (pin "P$20") (pinfunction "UP_P$20") (pintype "bidirectional"))
    )
    (net (code "62") (name "unconnected-(IC4-(ICP1{slash}CLKO{slash}PTCXY)_PB0-Pad12)") (class "Default")
      (node (ref "IC4") (pin "12") (pinfunction "(ICP1/CLKO/PTCXY)_PB0_12") (pintype "bidirectional"))
    )
    (net (code "63") (name "unconnected-(IC4-(OC0A{slash}PTCXY{slash}AIN0)_PD6-Pad10)") (class "Default")
      (node (ref "IC4") (pin "10") (pinfunction "(OC0A/PTCXY/AIN0)_PD6_10") (pintype "bidirectional"))
    )
    (net (code "64") (name "unconnected-(IC4-(OC2B{slash}INT1{slash}PTCXY)_PD3-Pad1)") (class "Default")
      (node (ref "IC4") (pin "1") (pinfunction "(OC2B/INT1/PTCXY)_PD3_1") (pintype "bidirectional"))
    )
    (net (code "65") (name "unconnected-(IC4-(SCL1{slash}T4{slash}PTCXY)_PE1-Pad6)") (class "Default")
      (node (ref "IC4") (pin "6") (pinfunction "(SCL1/T4/PTCXY)_PE1_6") (pintype "bidirectional"))
    )
    (net (code "66") (name "unconnected-(IC4-(SDA1{slash}ICP4{slash}ACO{slash}PTCXY)_PE0-Pad3)") (class "Default")
      (node (ref "IC4") (pin "3") (pinfunction "(SDA1/ICP4/ACO/PTCXY)_PE0_3") (pintype "bidirectional"))
    )
    (net (code "67") (name "unconnected-(IC4-(XCK0{slash}T0{slash}PTCXY)_PD4-Pad2)") (class "Default")
      (node (ref "IC4") (pin "2") (pinfunction "(XCK0/T0/PTCXY)_PD4_2") (pintype "bidirectional"))
    )
    (net (code "68") (name "unconnected-(IC4-AREF-Pad20)") (class "Default")
      (node (ref "IC4") (pin "20") (pinfunction "AREF_20") (pintype "bidirectional"))
    )
    (net (code "69") (name "unconnected-(IC4-PC3_(ADC3{slash}PTCY)-Pad26)") (class "Default")
      (node (ref "IC4") (pin "26") (pinfunction "PC3_(ADC3/PTCY)_26") (pintype "bidirectional"))
    )
    (net (code "70") (name "unconnected-(IC7-CLKOUT-Pad22)") (class "Default")
      (node (ref "IC7") (pin "22") (pinfunction "CLKOUT_22") (pintype "bidirectional"))
    )
    (net (code "71") (name "unconnected-(IC7-NC_1-Pad2)") (class "Default")
      (node (ref "IC7") (pin "2") (pinfunction "NC_1_2") (pintype "bidirectional"))
    )
    (net (code "72") (name "unconnected-(IC7-NC_2-Pad25)") (class "Default")
      (node (ref "IC7") (pin "25") (pinfunction "NC_2_25") (pintype "bidirectional"))
    )
    (net (code "73") (name "unconnected-(IC7-~{RX0BF}-Pad12)") (class "Default")
      (node (ref "IC7") (pin "12") (pinfunction "~{RX0BF}_12") (pintype "bidirectional"))
    )
    (net (code "74") (name "unconnected-(IC7-~{RX1BF}-Pad11)") (class "Default")
      (node (ref "IC7") (pin "11") (pinfunction "~{RX1BF}_11") (pintype "bidirectional"))
    )
    (net (code "75") (name "unconnected-(IC7-~{TX0RTS}-Pad23)") (class "Default")
      (node (ref "IC7") (pin "23") (pinfunction "~{TX0RTS}_23") (pintype "bidirectional"))
    )
    (net (code "76") (name "unconnected-(IC7-~{TX1RTS}-Pad6)") (class "Default")
      (node (ref "IC7") (pin "6") (pinfunction "~{TX1RTS}_6") (pintype "bidirectional"))
    )
    (net (code "77") (name "unconnected-(IC7-~{TX2RTS}-Pad7)") (class "Default")
      (node (ref "IC7") (pin "7") (pinfunction "~{TX2RTS}_7") (pintype "bidirectional"))
    )
    (net (code "78") (name "unconnected-(SV1-Pad5)") (class "Default")
      (node (ref "SV1") (pin "5") (pinfunction "5_5") (pintype "passive"))
    )
  )
)
